# controle_motor_official.net
KiCad netlist of a schematic drawn in Altium Designer
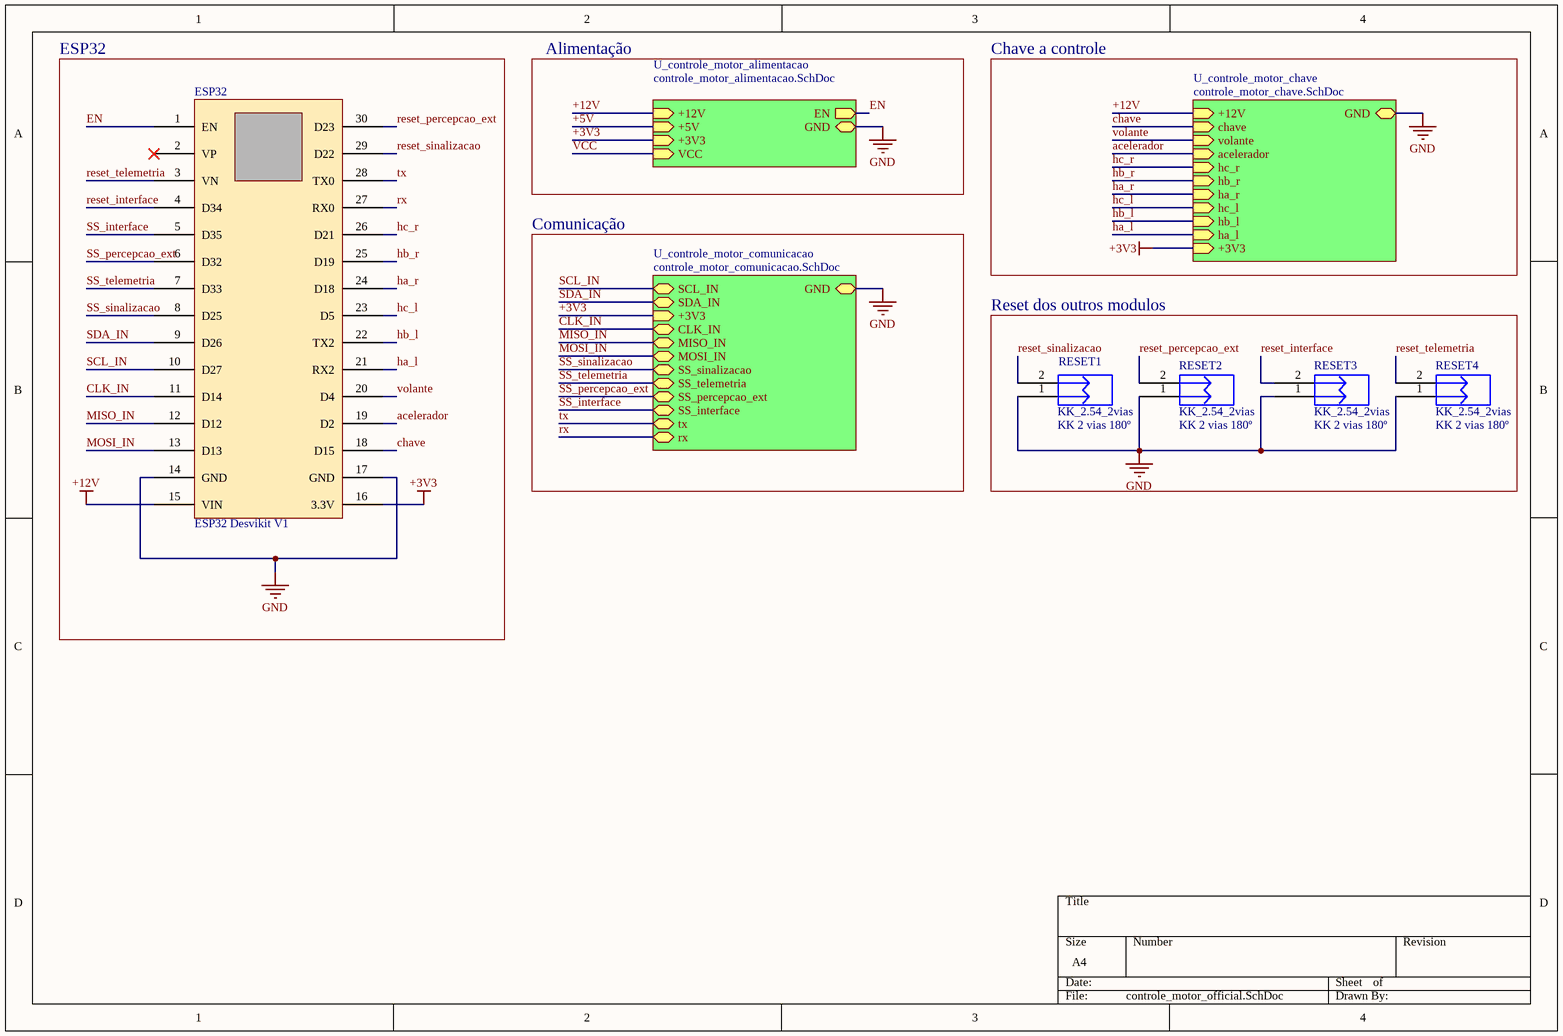
[diagram p0: controle_motor_official.SchDoc]

(export (version "E")
  (design (tool "Eeschema 10.0.6"))
  (components
    (comp (ref "ESP32")
      (value "ESP32 Desvikit V1")
      (footprint "ESP32_Desvikit_v1")
      (description "microcontrolador com moculo bluethoth e wifi")
      (fields (field (name "Comment") "microcontrolador"))
      (libsource (lib "Sinaliza玢o_Official") (part "ESP32 Desvikit v1"))
    )
    (comp (ref "RESET1")
      (value "KK_2.54_2vias")
      (footprint "KK_2VIAS_180º")
      (description "Conector KK 2.54mm 2 vias")
      (fields (field (name "VALOR") "KK 2 vias 180º"))
      (libsource (lib "Conectores_Sch") (part "KK_2.54_2vias"))
    )
    (comp (ref "RESET2")
      (value "KK_2.54_2vias")
      (footprint "KK_2VIAS_180º")
      (description "Conector KK 2.54mm 2 vias")
      (fields (field (name "VALOR") "KK 2 vias 180º"))
      (libsource (lib "Conectores_Sch") (part "KK_2.54_2vias"))
    )
    (comp (ref "RESET3")
      (value "KK_2.54_2vias")
      (footprint "KK_2VIAS_180º")
      (description "Conector KK 2.54mm 2 vias")
      (fields (field (name "VALOR") "KK 2 vias 180º"))
      (libsource (lib "Conectores_Sch") (part "KK_2.54_2vias"))
    )
    (comp (ref "RESET4")
      (value "KK_2.54_2vias")
      (footprint "KK_2VIAS_180º")
      (description "Conector KK 2.54mm 2 vias")
      (fields (field (name "VALOR") "KK 2 vias 180º"))
      (libsource (lib "Conectores_Sch") (part "KK_2.54_2vias"))
    )
  )
  (nets
    (net (code "1") (name "+3V3") (class "Default")
      (node (ref "ESP32") (pin "16") (pinfunction "3.3V_16") (pintype "passive"))
    )
    (net (code "2") (name "+12V") (class "Default")
      (node (ref "ESP32") (pin "15") (pinfunction "VIN_15") (pintype "passive"))
    )
    (net (code "4") (name "/CLK_IN") (class "Default")
      (node (ref "ESP32") (pin "11") (pinfunction "D14_11") (pintype "passive"))
    )
    (net (code "5") (name "/EN") (class "Default")
      (node (ref "ESP32") (pin "1") (pinfunction "EN_1") (pintype "passive"))
    )
    (net (code "6") (name "/MISO_IN") (class "Default")
      (node (ref "ESP32") (pin "12") (pinfunction "D12_12") (pintype "passive"))
    )
    (net (code "7") (name "/MOSI_IN") (class "Default")
      (node (ref "ESP32") (pin "13") (pinfunction "D13_13") (pintype "passive"))
    )
    (net (code "8") (name "/SCL_IN") (class "Default")
      (node (ref "ESP32") (pin "10") (pinfunction "D27_10") (pintype "passive"))
    )
    (net (code "9") (name "/SDA_IN") (class "Default")
      (node (ref "ESP32") (pin "9") (pinfunction "D26_9") (pintype "passive"))
    )
    (net (code "10") (name "/SS_interface") (class "Default")
      (node (ref "ESP32") (pin "5") (pinfunction "D35_5") (pintype "passive"))
    )
    (net (code "11") (name "/SS_percepcao_ext") (class "Default")
      (node (ref "ESP32") (pin "6") (pinfunction "D32_6") (pintype "passive"))
    )
    (net (code "12") (name "/SS_sinalizacao") (class "Default")
      (node (ref "ESP32") (pin "8") (pinfunction "D25_8") (pintype "passive"))
    )
    (net (code "13") (name "/SS_telemetria") (class "Default")
      (node (ref "ESP32") (pin "7") (pinfunction "D33_7") (pintype "passive"))
    )
    (net (code "15") (name "/acelerador") (class "Default")
      (node (ref "ESP32") (pin "19") (pinfunction "D2_19") (pintype "passive"))
    )
    (net (code "16") (name "/chave") (class "Default")
      (node (ref "ESP32") (pin "18") (pinfunction "D15_18") (pintype "passive"))
    )
    (net (code "17") (name "/ha_l") (class "Default")
      (node (ref "ESP32") (pin "21") (pinfunction "RX2_21") (pintype "passive"))
    )
    (net (code "18") (name "/ha_r") (class "Default")
      (node (ref "ESP32") (pin "24") (pinfunction "D18_24") (pintype "passive"))
    )
    (net (code "19") (name "/hb_l") (class "Default")
      (node (ref "ESP32") (pin "22") (pinfunction "TX2_22") (pintype "passive"))
    )
    (net (code "20") (name "/hb_r") (class "Default")
      (node (ref "ESP32") (pin "25") (pinfunction "D19_25") (pintype "passive"))
    )
    (net (code "21") (name "/hc_l") (class "Default")
      (node (ref "ESP32") (pin "23") (pinfunction "D5_23") (pintype "passive"))
    )
    (net (code "22") (name "/hc_r") (class "Default")
      (node (ref "ESP32") (pin "26") (pinfunction "D21_26") (pintype "passive"))
    )
    (net (code "23") (name "/reset_interface") (class "Default")
      (node (ref "ESP32") (pin "4") (pinfunction "D34_4") (pintype "passive"))
      (node (ref "RESET3") (pin "2") (pintype "passive"))
    )
    (net (code "24") (name "/reset_percepcao_ext") (class "Default")
      (node (ref "ESP32") (pin "30") (pinfunction "D23_30") (pintype "passive"))
      (node (ref "RESET2") (pin "2") (pintype "passive"))
    )
    (net (code "25") (name "/reset_sinalizacao") (class "Default")
      (node (ref "ESP32") (pin "29") (pinfunction "D22_29") (pintype "passive"))
      (node (ref "RESET1") (pin "2") (pintype "passive"))
    )
    (net (code "26") (name "/reset_telemetria") (class "Default")
      (node (ref "ESP32") (pin "3") (pinfunction "VN_3") (pintype "passive"))
      (node (ref "RESET4") (pin "2") (pintype "passive"))
    )
    (net (code "27") (name "/rx") (class "Default")
      (node (ref "ESP32") (pin "27") (pinfunction "RX0_27") (pintype "passive"))
    )
    (net (code "28") (name "/tx") (class "Default")
      (node (ref "ESP32") (pin "28") (pinfunction "TX0_28") (pintype "passive"))
    )
    (net (code "29") (name "/volante") (class "Default")
      (node (ref "ESP32") (pin "20") (pinfunction "D4_20") (pintype "passive"))
    )
    (net (code "30") (name "GND") (class "Default")
      (node (ref "ESP32") (pin "14") (pinfunction "GND_14") (pintype "passive"))
      (node (ref "ESP32") (pin "17") (pinfunction "GND_17") (pintype "passive"))
      (node (ref "RESET1") (pin "1") (pintype "passive"))
      (node (ref "RESET2") (pin "1") (pintype "passive"))
      (node (ref "RESET3") (pin "1") (pintype "passive"))
      (node (ref "RESET4") (pin "1") (pintype "passive"))
    )
    (net (code "31") (name "unconnected-(ESP32-VP-Pad2)") (class "Default")
      (node (ref "ESP32") (pin "2") (pinfunction "VP_2") (pintype "passive+no_connect"))
    )
  )
)
